# limit_switches_connector.net
KiCad netlist of a schematic drawn in Altium Designer
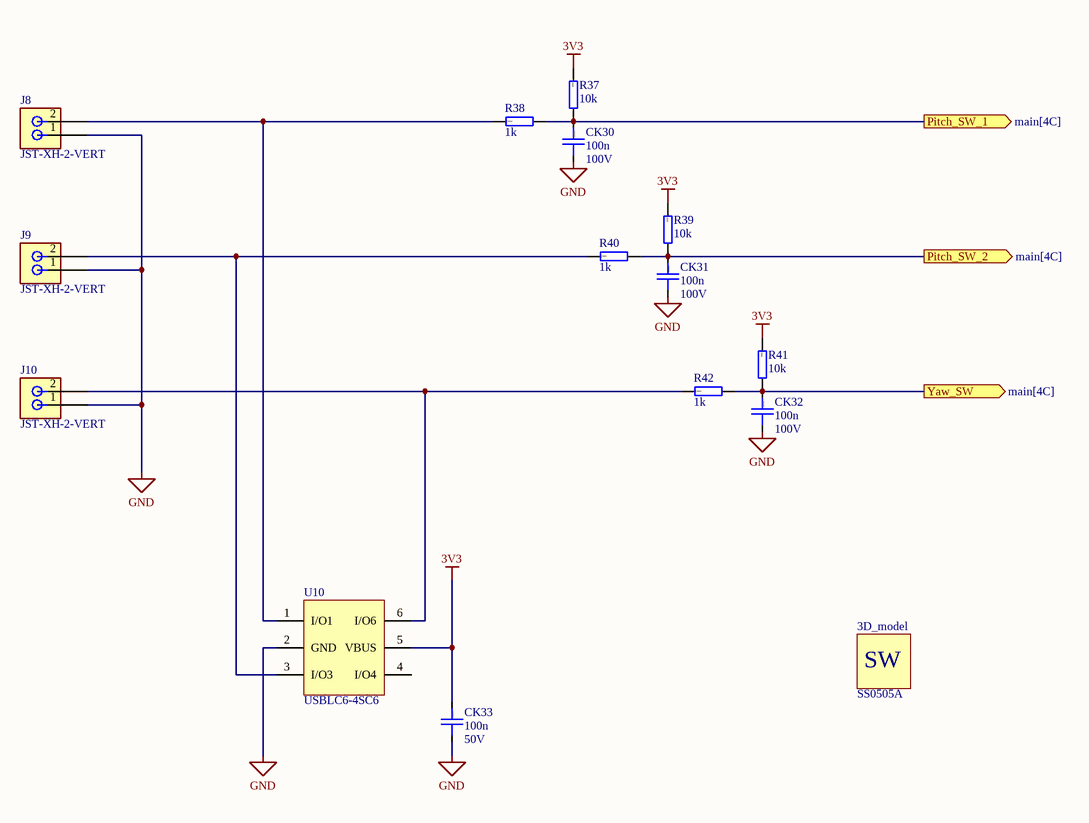
[diagram p0: limit_switches_connector.SchDoc]

(export (version "E")
  (design (tool "Eeschema 10.0.6"))
  (components
    (comp (ref "3D_model")
      (value "SS0505A")
      (footprint "limit_sw_model")
      (description "Mikrospínač SNAP ACTION; 3A/250VAC; s páčkou (s kladkou); SPDT")
      (fields (field (name "TME PART") "WLK-4MINI/HE"))
      (libsource (lib "Kubikova ultra knihovna") (part "model_only_limit_sw"))
    )
    (comp (ref "CK30")
      (value "100n")
      (footprint "CAP0805")
      (description "100V 100nF X7R ±10% 0805 Multilayer Ceramic Capacitors MLCC - SMD/SMT ROHS")
      (fields (field (name "JLCPCB PART") "C28233") (field (name "VOLTAGE RATING") "100V"))
      (libsource (lib "Kubikova ultra knihovna") (part "Cap 100n 100V 0805"))
    )
    (comp (ref "CK31")
      (value "100n")
      (footprint "CAP0805")
      (description "100V 100nF X7R ±10% 0805 Multilayer Ceramic Capacitors MLCC - SMD/SMT ROHS")
      (fields (field (name "JLCPCB PART") "C28233") (field (name "VOLTAGE RATING") "100V"))
      (libsource (lib "Kubikova ultra knihovna") (part "Cap 100n 100V 0805"))
    )
    (comp (ref "CK32")
      (value "100n")
      (footprint "CAP0805")
      (description "100V 100nF X7R ±10% 0805 Multilayer Ceramic Capacitors MLCC - SMD/SMT ROHS")
      (fields (field (name "JLCPCB PART") "C28233") (field (name "VOLTAGE RATING") "100V"))
      (libsource (lib "Kubikova ultra knihovna") (part "Cap 100n 100V 0805"))
    )
    (comp (ref "CK33")
      (value "100n")
      (footprint "CAP0603")
      (description "50V 100nF X7R ±10% 0603 Multilayer Ceramic Capacitors MLCC - SMD/SMT ROHS")
      (fields (field (name "JLCPCB PART") "C14663") (field (name "VOLTAGE RATING") "50V"))
      (libsource (lib "Kubikova ultra knihovna") (part "Cap 100n 0603"))
    )
    (comp (ref "J8")
      (value "JST-XH-2-VERT")
      (footprint "JST-XH-2p-vert")
      (description "Konektor: kabel-pl.spoj; zásuvka; vidlice; PIN: 2; XH; 3A; 250V; THT")
      (fields (field (name "TME PART") "B2B-XH-A"))
      (libsource (lib "Kubikova ultra knihovna") (part "JST-XH-2-VERT"))
    )
    (comp (ref "J9")
      (value "JST-XH-2-VERT")
      (footprint "JST-XH-2p-vert")
      (description "Konektor: kabel-pl.spoj; zásuvka; vidlice; PIN: 2; XH; 3A; 250V; THT")
      (fields (field (name "TME PART") "B2B-XH-A"))
      (libsource (lib "Kubikova ultra knihovna") (part "JST-XH-2-VERT"))
    )
    (comp (ref "J10")
      (value "JST-XH-2-VERT")
      (footprint "JST-XH-2p-vert")
      (description "Konektor: kabel-pl.spoj; zásuvka; vidlice; PIN: 2; XH; 3A; 250V; THT")
      (fields (field (name "TME PART") "B2B-XH-A"))
      (libsource (lib "Kubikova ultra knihovna") (part "JST-XH-2-VERT"))
    )
    (comp (ref "R37")
      (value "10k")
      (footprint "RESC2012X06N(SMR0805)")
      (description "125mW Thick Film Resistors 150V ±100ppm/℃ ±1% 10kΩ 0805 Chip Resistor - Surface Mount ROHS")
      (fields (field (name "JLCPCB PART") "C17414"))
      (libsource (lib "Kubikova ultra knihovna") (part "Res 10k 0805"))
    )
    (comp (ref "R38")
      (value "1k")
      (footprint "RESC2012X06N(SMR0805)")
      (description "125mW Thick Film Resistors 150V ±100ppm/℃ ±1% 1kΩ 0805 Chip Resistor - Surface Mount ROHS")
      (fields (field (name "JLCPCB PART") "C17513") (field (name "AUTHOR") "JP/27.03.2014"))
      (libsource (lib "Kubikova ultra knihovna") (part "Res 1k 0805"))
    )
    (comp (ref "R39")
      (value "10k")
      (footprint "RESC2012X06N(SMR0805)")
      (description "125mW Thick Film Resistors 150V ±100ppm/℃ ±1% 10kΩ 0805 Chip Resistor - Surface Mount ROHS")
      (fields (field (name "JLCPCB PART") "C17414"))
      (libsource (lib "Kubikova ultra knihovna") (part "Res 10k 0805"))
    )
    (comp (ref "R40")
      (value "1k")
      (footprint "RESC2012X06N(SMR0805)")
      (description "125mW Thick Film Resistors 150V ±100ppm/℃ ±1% 1kΩ 0805 Chip Resistor - Surface Mount ROHS")
      (fields (field (name "JLCPCB PART") "C17513") (field (name "AUTHOR") "JP/27.03.2014"))
      (libsource (lib "Kubikova ultra knihovna") (part "Res 1k 0805"))
    )
    (comp (ref "R41")
      (value "10k")
      (footprint "RESC2012X06N(SMR0805)")
      (description "125mW Thick Film Resistors 150V ±100ppm/℃ ±1% 10kΩ 0805 Chip Resistor - Surface Mount ROHS")
      (fields (field (name "JLCPCB PART") "C17414"))
      (libsource (lib "Kubikova ultra knihovna") (part "Res 10k 0805"))
    )
    (comp (ref "R42")
      (value "1k")
      (footprint "RESC2012X06N(SMR0805)")
      (description "125mW Thick Film Resistors 150V ±100ppm/℃ ±1% 1kΩ 0805 Chip Resistor - Surface Mount ROHS")
      (fields (field (name "JLCPCB PART") "C17513") (field (name "AUTHOR") "JP/27.03.2014"))
      (libsource (lib "Kubikova ultra knihovna") (part "Res 1k 0805"))
    )
    (comp (ref "U10")
      (value "USBLC6-4SC6")
      (footprint "SOT23-6")
      (description "5A 17V 6V Unidirectional 5.25V SOT-23-6 ESD and Surge Protection (TVS/ESD) ROHS")
      (fields (field (name "JLCPCB PART") "C111212"))
      (libsource (lib "Kubikova ultra knihovna") (part "USBLC6-4SC6"))
    )
  )
  (nets
    (net (code "1") (name "/Pitch_SW_1") (class "Default")
      (node (ref "CK30") (pin "1") (pinfunction "1_1") (pintype "passive"))
      (node (ref "R37") (pin "1") (pinfunction "1_1") (pintype "passive"))
      (node (ref "R38") (pin "1") (pinfunction "1_1") (pintype "passive"))
    )
    (net (code "2") (name "/Pitch_SW_2") (class "Default")
      (node (ref "CK31") (pin "1") (pinfunction "1_1") (pintype "passive"))
      (node (ref "R39") (pin "1") (pinfunction "1_1") (pintype "passive"))
      (node (ref "R40") (pin "1") (pinfunction "1_1") (pintype "passive"))
    )
    (net (code "3") (name "/Yaw_SW") (class "Default")
      (node (ref "CK32") (pin "1") (pinfunction "1_1") (pintype "passive"))
      (node (ref "R41") (pin "1") (pinfunction "1_1") (pintype "passive"))
      (node (ref "R42") (pin "1") (pinfunction "1_1") (pintype "passive"))
    )
    (net (code "4") (name "3V3") (class "Default")
      (node (ref "CK33") (pin "1") (pinfunction "1_1") (pintype "passive"))
      (node (ref "R37") (pin "2") (pinfunction "2_2") (pintype "passive"))
      (node (ref "R39") (pin "2") (pinfunction "2_2") (pintype "passive"))
      (node (ref "R41") (pin "2") (pinfunction "2_2") (pintype "passive"))
      (node (ref "U10") (pin "5") (pinfunction "VBUS_5") (pintype "passive"))
    )
    (net (code "5") (name "GND") (class "Default")
      (node (ref "CK30") (pin "2") (pinfunction "2_2") (pintype "passive"))
      (node (ref "CK31") (pin "2") (pinfunction "2_2") (pintype "passive"))
      (node (ref "CK32") (pin "2") (pinfunction "2_2") (pintype "passive"))
      (node (ref "CK33") (pin "2") (pinfunction "2_2") (pintype "passive"))
      (node (ref "J10") (pin "1") (pinfunction "1_1") (pintype "passive"))
      (node (ref "J8") (pin "1") (pinfunction "1_1") (pintype "passive"))
      (node (ref "J9") (pin "1") (pinfunction "1_1") (pintype "passive"))
      (node (ref "U10") (pin "2") (pinfunction "GND_2") (pintype "passive"))
    )
    (net (code "6") (name "Net-(U10-I{slash}O1)") (class "Default")
      (node (ref "J8") (pin "2") (pinfunction "2_2") (pintype "passive"))
      (node (ref "R38") (pin "2") (pinfunction "2_2") (pintype "passive"))
      (node (ref "U10") (pin "1") (pinfunction "I/O1_1") (pintype "passive"))
    )
    (net (code "7") (name "Net-(U10-I{slash}O3)") (class "Default")
      (node (ref "J9") (pin "2") (pinfunction "2_2") (pintype "passive"))
      (node (ref "R40") (pin "2") (pinfunction "2_2") (pintype "passive"))
      (node (ref "U10") (pin "3") (pinfunction "I/O3_3") (pintype "passive"))
    )
    (net (code "8") (name "Net-(U10-I{slash}O6)") (class "Default")
      (node (ref "J10") (pin "2") (pinfunction "2_2") (pintype "passive"))
      (node (ref "R42") (pin "2") (pinfunction "2_2") (pintype "passive"))
      (node (ref "U10") (pin "6") (pinfunction "I/O6_6") (pintype "passive"))
    )
    (net (code "9") (name "unconnected-(U10-I{slash}O4-Pad4)") (class "Default")
      (node (ref "U10") (pin "4") (pinfunction "I/O4_4") (pintype "passive"))
    )
  )
)
